# light.net
KiCad netlist of a schematic drawn in EAGLE
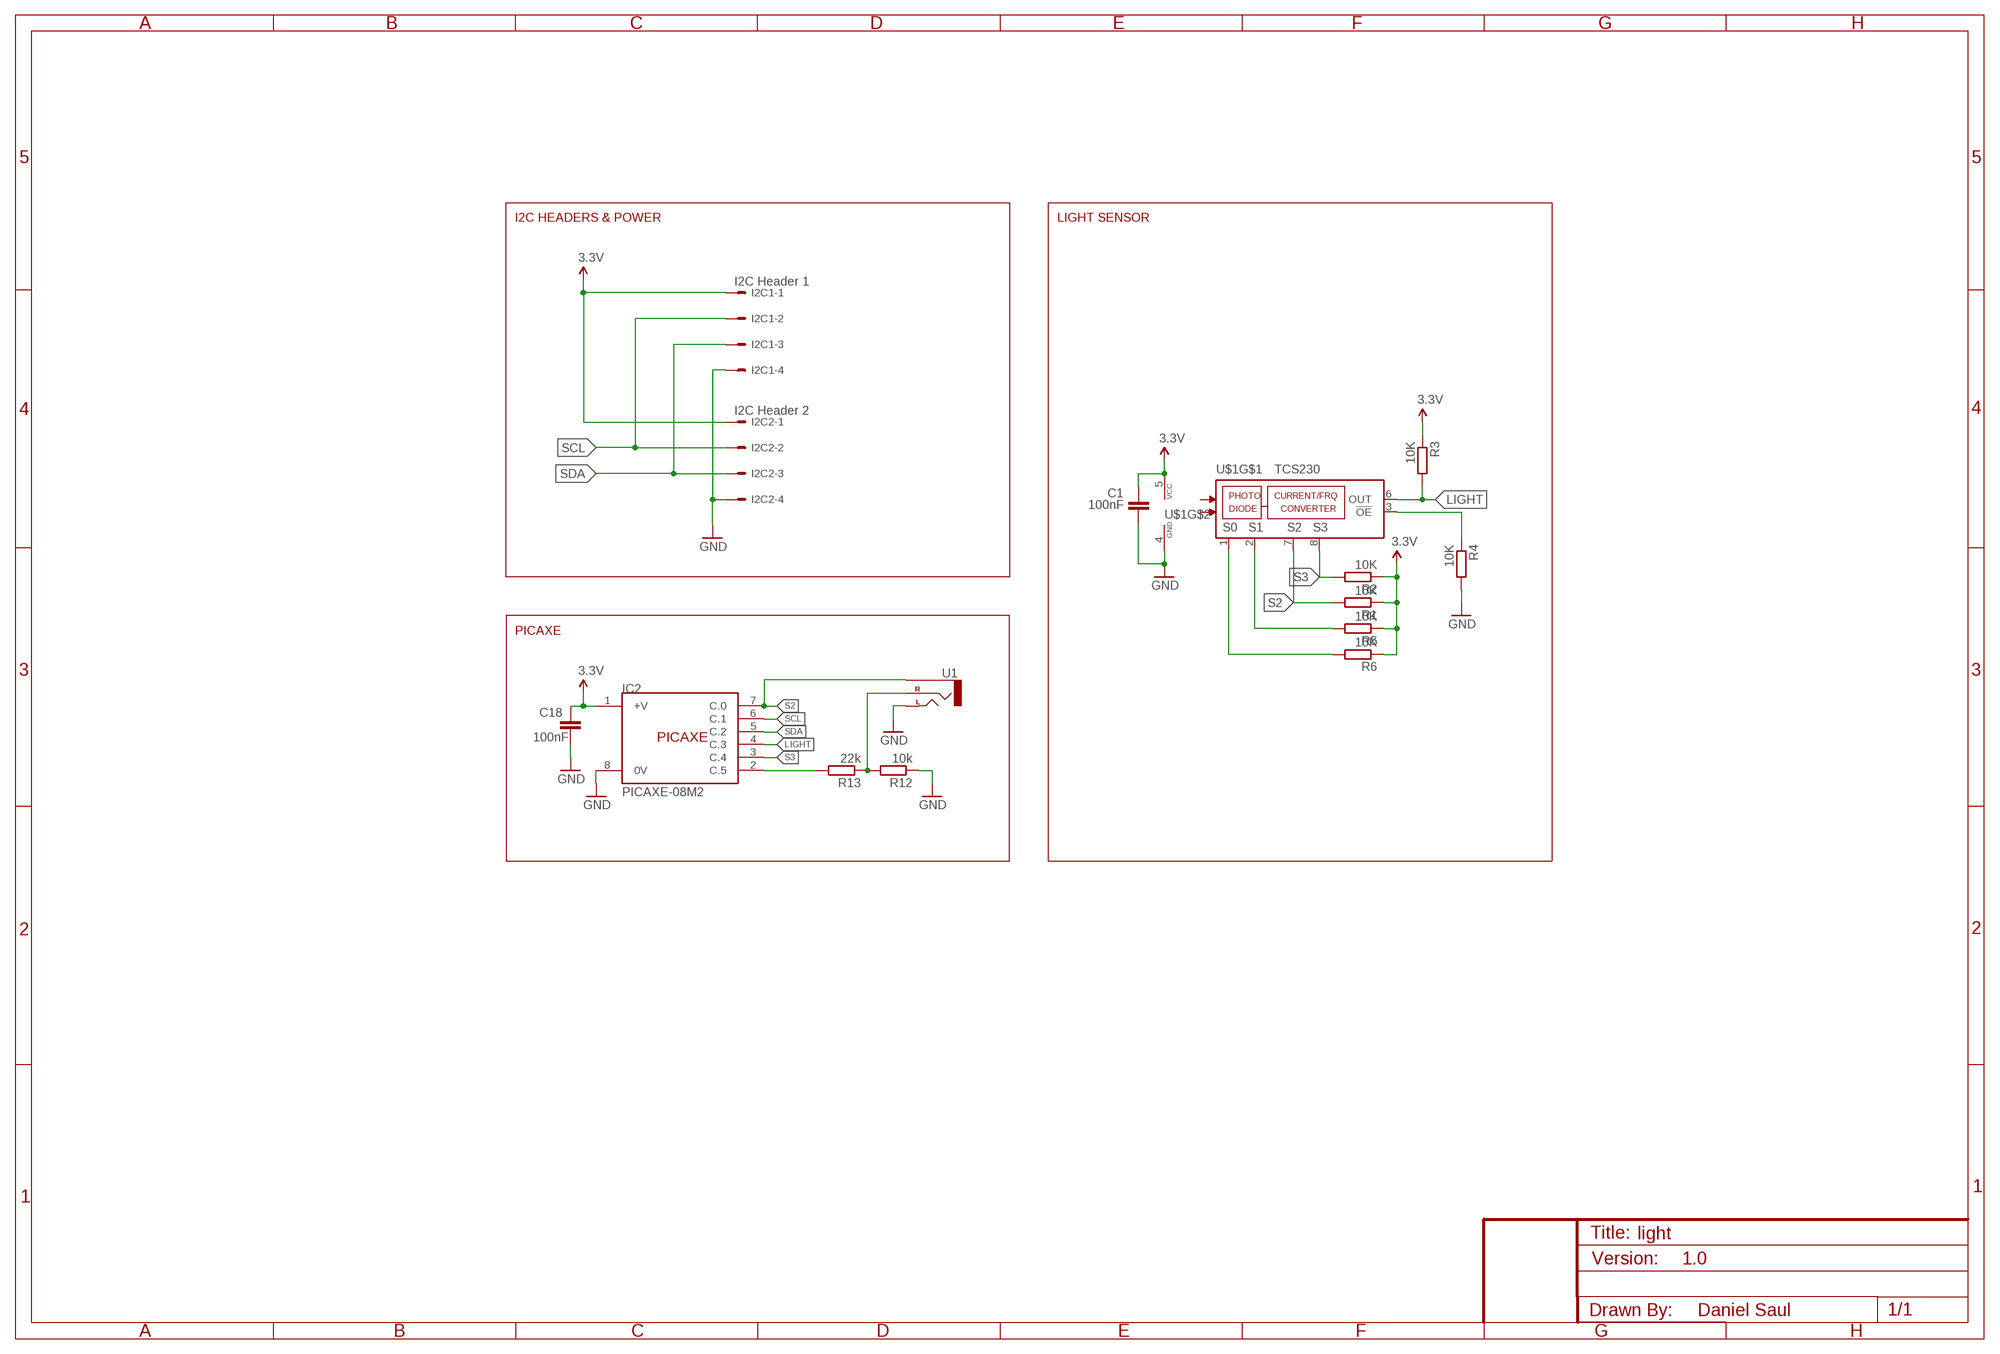
[diagram p0: schematic, sheet 1]

(export (version "E")
  (design (tool "Eeschema 10.0.6"))
  (components
    (comp (ref "C1")
      (value "100nF")
      (footprint "eagle-import:C0805")
      (libsource (lib "eagle-import") (part "C-EUC0805"))
    )
    (comp (ref "C18")
      (value "100nF")
      (footprint "eagle-import:C0805")
      (libsource (lib "eagle-import") (part "C-EUC0805"))
    )
    (comp (ref "I2C1")
      (value "I2C Header 1")
      (footprint "eagle-import:6410-04")
      (libsource (lib "eagle-import") (part "22-?-0427-2041"))
    )
    (comp (ref "I2C2")
      (value "I2C Header 2")
      (footprint "eagle-import:6410-04")
      (libsource (lib "eagle-import") (part "22-?-0427-2041"))
    )
    (comp (ref "IC2")
      (value "PICAXE-08M2")
      (footprint "eagle-import:SOIC8")
      (libsource (lib "eagle-import") (part "PICAXE-08M2"))
    )
    (comp (ref "R1")
      (value "10K")
      (footprint "eagle-import:R0805")
      (libsource (lib "eagle-import") (part "R-EU_R0805"))
    )
    (comp (ref "R2")
      (value "10K")
      (footprint "eagle-import:R0805")
      (libsource (lib "eagle-import") (part "R-EU_R0805"))
    )
    (comp (ref "R3")
      (value "10K")
      (footprint "eagle-import:R0805")
      (libsource (lib "eagle-import") (part "R-EU_R0805"))
    )
    (comp (ref "R4")
      (value "10K")
      (footprint "eagle-import:R0805")
      (libsource (lib "eagle-import") (part "R-EU_R0805"))
    )
    (comp (ref "R5")
      (value "10K")
      (footprint "eagle-import:R0805")
      (libsource (lib "eagle-import") (part "R-EU_R0805"))
    )
    (comp (ref "R6")
      (value "10K")
      (footprint "eagle-import:R0805")
      (libsource (lib "eagle-import") (part "R-EU_R0805"))
    )
    (comp (ref "R12")
      (value "10k")
      (footprint "eagle-import:R0805")
      (libsource (lib "eagle-import") (part "R-EU_R0805"))
    )
    (comp (ref "R13")
      (value "22k")
      (footprint "eagle-import:R0805")
      (libsource (lib "eagle-import") (part "R-EU_R0805"))
    )
    (comp (ref "U$1")
      (value "TCS230")
      (footprint "eagle-import:SOIC8")
      (libsource (lib "eagle-import") (part "TCS230"))
    )
    (comp (ref "U1")
      (value "AUDIO-JACKPTH")
      (footprint "eagle-import:AUDIO-JACK")
      (libsource (lib "eagle-import") (part "AUDIO-JACKPTH"))
    )
  )
  (nets
    (net (code "1") (name "3.3V") (class "Default")
      (node (ref "C1") (pin "1") (pinfunction "1_1") (pintype "passive"))
      (node (ref "C18") (pin "1") (pinfunction "1_1") (pintype "passive"))
      (node (ref "I2C1") (pin "1") (pinfunction "S_1") (pintype "passive"))
      (node (ref "I2C2") (pin "1") (pinfunction "S_1") (pintype "passive"))
      (node (ref "IC2") (pin "1") (pinfunction "+V_1") (pintype "power_in"))
      (node (ref "R1") (pin "1") (pinfunction "1_1") (pintype "passive"))
      (node (ref "R2") (pin "1") (pinfunction "1_1") (pintype "passive"))
      (node (ref "R3") (pin "1") (pinfunction "1_1") (pintype "passive"))
      (node (ref "R5") (pin "1") (pinfunction "1_1") (pintype "passive"))
      (node (ref "R6") (pin "1") (pinfunction "1_1") (pintype "passive"))
      (node (ref "U$1") (pin "5") (pinfunction "VCC_5") (pintype "power_in"))
    )
    (net (code "2") (name "GND") (class "Default")
      (node (ref "C1") (pin "2") (pinfunction "2_2") (pintype "passive"))
      (node (ref "C18") (pin "2") (pinfunction "2_2") (pintype "passive"))
      (node (ref "I2C1") (pin "4") (pinfunction "S_4") (pintype "passive"))
      (node (ref "I2C2") (pin "4") (pinfunction "S_4") (pintype "passive"))
      (node (ref "IC2") (pin "8") (pinfunction "0V_8") (pintype "power_in"))
      (node (ref "R12") (pin "1") (pinfunction "1_1") (pintype "passive"))
      (node (ref "R4") (pin "2") (pinfunction "2_2") (pintype "passive"))
      (node (ref "U$1") (pin "4") (pinfunction "GND_4") (pintype "power_in"))
      (node (ref "U1") (pin "TIP") (pinfunction "LEFT_TIP") (pintype "bidirectional"))
    )
    (net (code "3") (name "LIGHT") (class "Default")
      (node (ref "IC2") (pin "4") (pinfunction "C.3_4") (pintype "bidirectional"))
      (node (ref "R3") (pin "2") (pinfunction "2_2") (pintype "passive"))
      (node (ref "U$1") (pin "6") (pinfunction "OUT_6") (pintype "output"))
    )
    (net (code "4") (name "Net-(IC2-C.5)") (class "Default")
      (node (ref "IC2") (pin "2") (pinfunction "C.5_2") (pintype "bidirectional"))
      (node (ref "R13") (pin "2") (pinfunction "2_2") (pintype "passive"))
    )
    (net (code "5") (name "Net-(U$1A-S0)") (class "Default")
      (node (ref "R6") (pin "2") (pinfunction "2_2") (pintype "passive"))
      (node (ref "U$1") (pin "1") (pinfunction "S0_1") (pintype "input"))
    )
    (net (code "6") (name "Net-(U$1A-S1)") (class "Default")
      (node (ref "R5") (pin "2") (pinfunction "2_2") (pintype "passive"))
      (node (ref "U$1") (pin "2") (pinfunction "S1_2") (pintype "input"))
    )
    (net (code "7") (name "Net-(U$1A-~{OE})") (class "Default")
      (node (ref "R4") (pin "1") (pinfunction "1_1") (pintype "passive"))
      (node (ref "U$1") (pin "3") (pinfunction "~{OE}_3") (pintype "input"))
    )
    (net (code "8") (name "Net-(U1-RIGHT)") (class "Default")
      (node (ref "R12") (pin "2") (pinfunction "2_2") (pintype "passive"))
      (node (ref "R13") (pin "1") (pinfunction "1_1") (pintype "passive"))
      (node (ref "U1") (pin "RING") (pinfunction "RIGHT_RING") (pintype "bidirectional"))
    )
    (net (code "9") (name "S2") (class "Default")
      (node (ref "IC2") (pin "7") (pinfunction "C.0_7") (pintype "bidirectional"))
      (node (ref "R1") (pin "2") (pinfunction "2_2") (pintype "passive"))
      (node (ref "U$1") (pin "7") (pinfunction "S2_7") (pintype "input"))
      (node (ref "U1") (pin "SLEEVE") (pinfunction "SLEEVE_SLEEVE") (pintype "bidirectional"))
    )
    (net (code "10") (name "S3") (class "Default")
      (node (ref "IC2") (pin "3") (pinfunction "C.4_3") (pintype "bidirectional"))
      (node (ref "R2") (pin "2") (pinfunction "2_2") (pintype "passive"))
      (node (ref "U$1") (pin "8") (pinfunction "S3_8") (pintype "input"))
    )
    (net (code "11") (name "SCL") (class "Default")
      (node (ref "I2C1") (pin "2") (pinfunction "S_2") (pintype "passive"))
      (node (ref "I2C2") (pin "2") (pinfunction "S_2") (pintype "passive"))
      (node (ref "IC2") (pin "6") (pinfunction "C.1_6") (pintype "bidirectional"))
    )
    (net (code "12") (name "SDA") (class "Default")
      (node (ref "I2C1") (pin "3") (pinfunction "S_3") (pintype "passive"))
      (node (ref "I2C2") (pin "3") (pinfunction "S_3") (pintype "passive"))
      (node (ref "IC2") (pin "5") (pinfunction "C.2_5") (pintype "bidirectional"))
    )
  )
)
